# Temctrl_CPU.net
KiCad netlist of a schematic drawn in Altium Designer
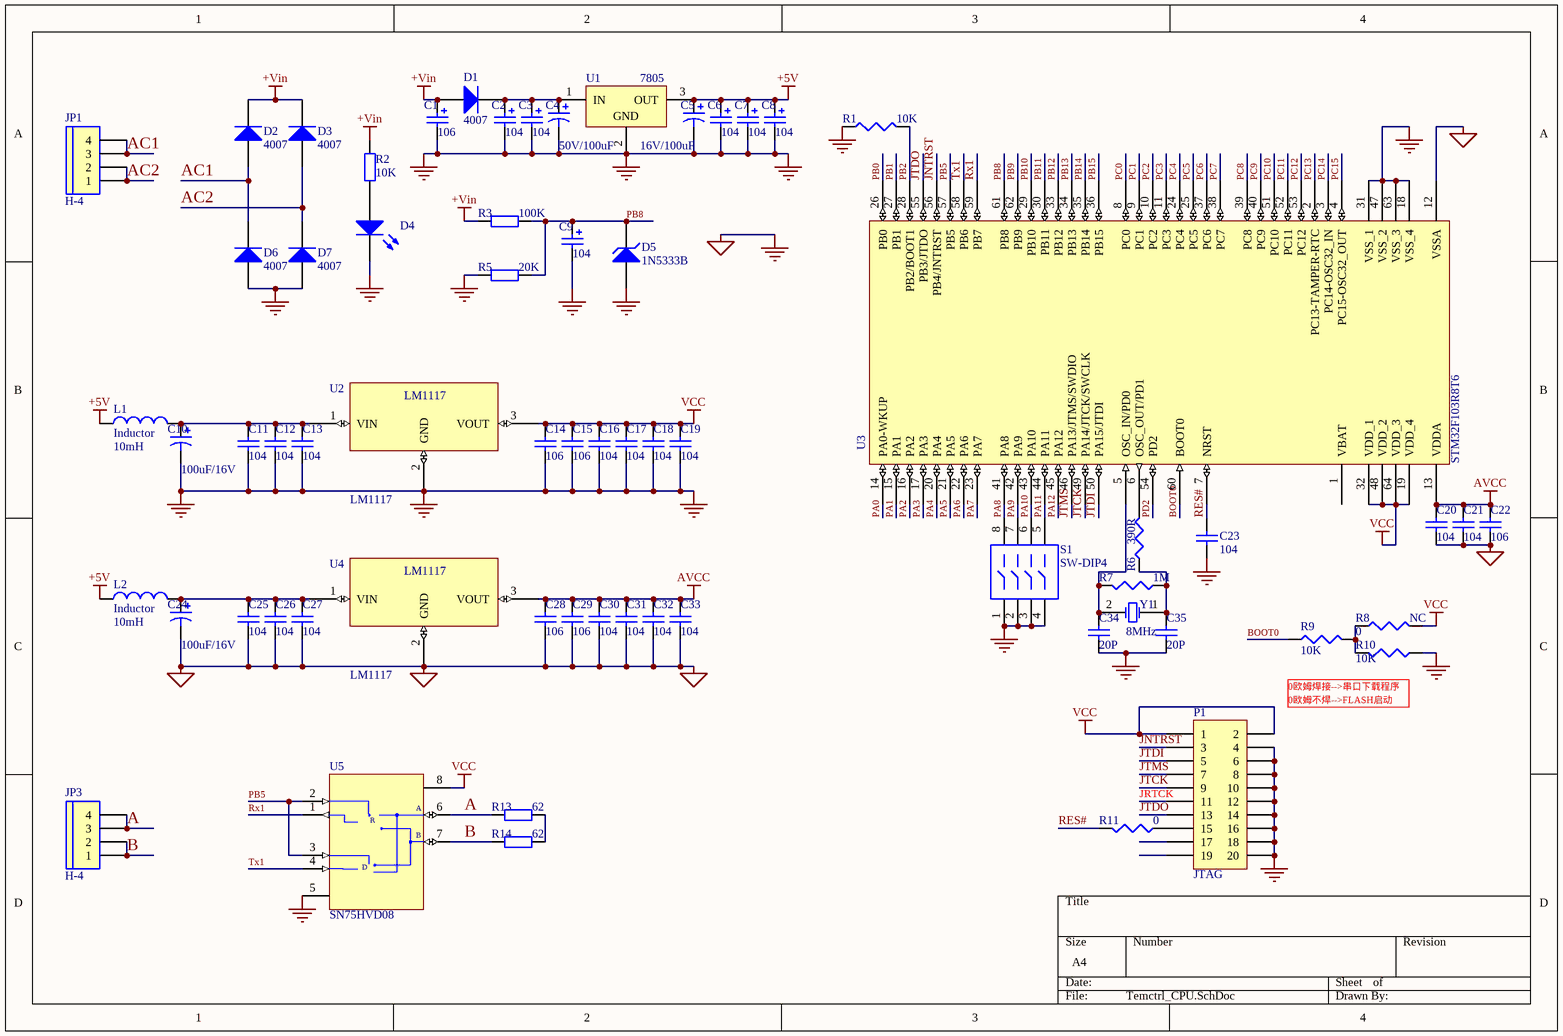
[diagram p0: Temctrl_CPU.SchDoc]

(export (version "E")
  (design (tool "Eeschema 10.0.6"))
  (components
    (comp (ref "C1")
      (value "106")
      (footprint "0805")
      (description "Polarized Capacitor (Axial)")
      (fields
        (field (name "MANUFACTURER") "Generic Components")
        (field (name "PUBLISHER") "Altium Hobart Technology Centre")
      )
      (libsource (lib "HGH") (part "Cap Pol2"))
    )
    (comp (ref "C2")
      (value "104")
      (footprint "0805")
      (description "Polarized Capacitor (Axial)")
      (fields
        (field (name "MANUFACTURER") "Generic Components")
        (field (name "PUBLISHER") "Altium Hobart Technology Centre")
      )
      (libsource (lib "HGH") (part "Cap Pol2"))
    )
    (comp (ref "C3")
      (value "104")
      (footprint "0805")
      (description "Polarized Capacitor (Axial)")
      (fields
        (field (name "MANUFACTURER") "Generic Components")
        (field (name "PUBLISHER") "Altium Hobart Technology Centre")
      )
      (libsource (lib "HGH") (part "Cap Pol2"))
    )
    (comp (ref "C4")
      (value "50V/100uF")
      (footprint "Temctrl:50V/100uF SOC")
      (description "Polarized Capacitor (Radial)")
      (fields (field (name "PUBLISHER") "Altium Limited"))
      (libsource (lib "Miscellaneous Devices") (part "Cap Pol1"))
    )
    (comp (ref "C5")
      (value "16V/100uF")
      (footprint "PCB封装库:100/16V   SOC")
      (description "Polarized Capacitor (Radial)")
      (fields (field (name "PUBLISHER") "Altium Limited"))
      (libsource (lib "Miscellaneous Devices") (part "Cap Pol1"))
    )
    (comp (ref "C6")
      (value "104")
      (footprint "0805")
      (description "Polarized Capacitor (Axial)")
      (fields
        (field (name "MANUFACTURER") "Generic Components")
        (field (name "PUBLISHER") "Altium Hobart Technology Centre")
      )
      (libsource (lib "HGH") (part "Cap Pol2"))
    )
    (comp (ref "C7")
      (value "104")
      (footprint "0805")
      (description "Polarized Capacitor (Axial)")
      (fields
        (field (name "MANUFACTURER") "Generic Components")
        (field (name "PUBLISHER") "Altium Hobart Technology Centre")
      )
      (libsource (lib "HGH") (part "Cap Pol2"))
    )
    (comp (ref "C8")
      (value "104")
      (footprint "0805")
      (description "Polarized Capacitor (Axial)")
      (fields
        (field (name "MANUFACTURER") "Generic Components")
        (field (name "PUBLISHER") "Altium Hobart Technology Centre")
      )
      (libsource (lib "HGH") (part "Cap Pol2"))
    )
    (comp (ref "C9")
      (value "104")
      (footprint "0805")
      (description "Polarized Capacitor (Axial)")
      (fields
        (field (name "MANUFACTURER") "Generic Components")
        (field (name "PUBLISHER") "Altium Hobart Technology Centre")
      )
      (libsource (lib "HGH") (part "Cap Pol2"))
    )
    (comp (ref "C10")
      (value "100uF/16V")
      (footprint "PCB封装库:100/16V   SOC")
      (description "Polarized Capacitor (Radial)")
      (fields (field (name "PUBLISHER") "Altium Limited"))
      (libsource (lib "Miscellaneous Devices") (part "Cap Pol1"))
    )
    (comp (ref "C11")
      (value "104")
      (footprint "0805")
      (description "Capacitor")
      (fields (field (name "PUBLISHER") "Altium Limited"))
      (libsource (lib "Miscellaneous Devices") (part "Cap"))
    )
    (comp (ref "C12")
      (value "104")
      (footprint "0805")
      (description "Capacitor")
      (fields (field (name "PUBLISHER") "Altium Limited"))
      (libsource (lib "Miscellaneous Devices") (part "Cap"))
    )
    (comp (ref "C13")
      (value "104")
      (footprint "0805")
      (description "Capacitor")
      (fields (field (name "PUBLISHER") "Altium Limited"))
      (libsource (lib "Miscellaneous Devices") (part "Cap"))
    )
    (comp (ref "C14")
      (value "106")
      (footprint "0805")
      (description "Capacitor")
      (fields (field (name "PUBLISHER") "Altium Limited"))
      (libsource (lib "Miscellaneous Devices") (part "Cap"))
    )
    (comp (ref "C15")
      (value "106")
      (footprint "0805")
      (description "Capacitor")
      (fields (field (name "PUBLISHER") "Altium Limited"))
      (libsource (lib "Miscellaneous Devices") (part "Cap"))
    )
    (comp (ref "C16")
      (value "104")
      (footprint "0805")
      (description "Capacitor")
      (fields (field (name "PUBLISHER") "Altium Limited"))
      (libsource (lib "Miscellaneous Devices") (part "Cap"))
    )
    (comp (ref "C17")
      (value "104")
      (footprint "0805")
      (description "Capacitor")
      (fields (field (name "PUBLISHER") "Altium Limited"))
      (libsource (lib "Miscellaneous Devices") (part "Cap"))
    )
    (comp (ref "C18")
      (value "104")
      (footprint "0805")
      (description "Capacitor")
      (fields (field (name "PUBLISHER") "Altium Limited"))
      (libsource (lib "Miscellaneous Devices") (part "Cap"))
    )
    (comp (ref "C19")
      (value "104")
      (footprint "0805")
      (description "Capacitor")
      (fields (field (name "PUBLISHER") "Altium Limited"))
      (libsource (lib "Miscellaneous Devices") (part "Cap"))
    )
    (comp (ref "C20")
      (value "104")
      (footprint "0805")
      (description "Capacitor (Semiconductor SIM Model)")
      (fields (field (name "PUBLISHER") "Altium Limited"))
      (libsource (lib "Miscellaneous Devices 04") (part "Cap Semi"))
    )
    (comp (ref "C21")
      (value "104")
      (footprint "0805")
      (description "Capacitor (Semiconductor SIM Model)")
      (fields (field (name "PUBLISHER") "Altium Limited"))
      (libsource (lib "Miscellaneous Devices 04") (part "Cap Semi"))
    )
    (comp (ref "C22")
      (value "106")
      (footprint "0805")
      (description "Capacitor (Semiconductor SIM Model)")
      (fields (field (name "PUBLISHER") "Altium Limited"))
      (libsource (lib "Miscellaneous Devices 04") (part "Cap Semi"))
    )
    (comp (ref "C23")
      (value "104")
      (footprint "0805")
      (description "Capacitor (Semiconductor SIM Model)")
      (fields (field (name "PUBLISHER") "Altium Limited"))
      (libsource (lib "Miscellaneous Devices 04") (part "Cap Semi"))
    )
    (comp (ref "C24")
      (value "100uF/16V")
      (footprint "PCB封装库:100/16V   SOC")
      (description "Polarized Capacitor (Radial)")
      (fields (field (name "PUBLISHER") "Altium Limited"))
      (libsource (lib "Miscellaneous Devices") (part "Cap Pol1"))
    )
    (comp (ref "C25")
      (value "104")
      (footprint "0805")
      (description "Capacitor")
      (fields (field (name "PUBLISHER") "Altium Limited"))
      (libsource (lib "Miscellaneous Devices") (part "Cap"))
    )
    (comp (ref "C26")
      (value "104")
      (footprint "0805")
      (description "Capacitor")
      (fields (field (name "PUBLISHER") "Altium Limited"))
      (libsource (lib "Miscellaneous Devices") (part "Cap"))
    )
    (comp (ref "C27")
      (value "104")
      (footprint "0805")
      (description "Capacitor")
      (fields (field (name "PUBLISHER") "Altium Limited"))
      (libsource (lib "Miscellaneous Devices") (part "Cap"))
    )
    (comp (ref "C28")
      (value "106")
      (footprint "0805")
      (description "Capacitor")
      (fields (field (name "PUBLISHER") "Altium Limited"))
      (libsource (lib "Miscellaneous Devices") (part "Cap"))
    )
    (comp (ref "C29")
      (value "106")
      (footprint "0805")
      (description "Capacitor")
      (fields (field (name "PUBLISHER") "Altium Limited"))
      (libsource (lib "Miscellaneous Devices") (part "Cap"))
    )
    (comp (ref "C30")
      (value "104")
      (footprint "0805")
      (description "Capacitor")
      (fields (field (name "PUBLISHER") "Altium Limited"))
      (libsource (lib "Miscellaneous Devices") (part "Cap"))
    )
    (comp (ref "C31")
      (value "104")
      (footprint "0805")
      (description "Capacitor")
      (fields (field (name "PUBLISHER") "Altium Limited"))
      (libsource (lib "Miscellaneous Devices") (part "Cap"))
    )
    (comp (ref "C32")
      (value "104")
      (footprint "0805")
      (description "Capacitor")
      (fields (field (name "PUBLISHER") "Altium Limited"))
      (libsource (lib "Miscellaneous Devices") (part "Cap"))
    )
    (comp (ref "C33")
      (value "104")
      (footprint "0805")
      (description "Capacitor")
      (fields (field (name "PUBLISHER") "Altium Limited"))
      (libsource (lib "Miscellaneous Devices") (part "Cap"))
    )
    (comp (ref "C34")
      (value "20P")
      (footprint "0805")
      (description "Capacitor (Semiconductor SIM Model)")
      (fields (field (name "PUBLISHER") "Altium Limited"))
      (libsource (lib "Miscellaneous Devices 04") (part "Cap Semi"))
    )
    (comp (ref "C35")
      (value "20P")
      (footprint "0805")
      (description "Capacitor (Semiconductor SIM Model)")
      (fields (field (name "PUBLISHER") "Altium Limited"))
      (libsource (lib "Miscellaneous Devices 04") (part "Cap Semi"))
    )
    (comp (ref "D1")
      (value "4007")
      (footprint "DIODE0.4")
      (description "Default Diode")
      (fields
        (field (name "MANUFACTURER") "Generic Components")
        (field (name "PUBLISHER") "Altium Hobart Technology Centre")
      )
      (libsource (lib "HGH") (part "Diode"))
    )
    (comp (ref "D2")
      (value "4007")
      (footprint "DIODE0.4")
      (description "Default Diode")
      (fields
        (field (name "MANUFACTURER") "Generic Components")
        (field (name "PUBLISHER") "Altium Hobart Technology Centre")
      )
      (libsource (lib "HGH") (part "Diode"))
    )
    (comp (ref "D3")
      (value "4007")
      (footprint "DIODE0.4")
      (description "Default Diode")
      (fields
        (field (name "MANUFACTURER") "Generic Components")
        (field (name "PUBLISHER") "Altium Hobart Technology Centre")
      )
      (libsource (lib "HGH") (part "Diode"))
    )
    (comp (ref "D4")
      (value "LED0")
      (footprint "LED0.1-0.22")
      (description "Typical INFRARED GaAs LED")
      (fields (field (name "PUBLISHER") "Altium Limited"))
      (libsource (lib "Miscellaneous Devices") (part "LED0"))
    )
    (comp (ref "D5")
      (value "1N5333B")
      (footprint "DIODE0.4")
      (description "Zener Diode")
      (fields (field (name "PUBLISHER") "Altium Limited"))
      (libsource (lib "Miscellaneous Devices") (part "D Zener"))
    )
    (comp (ref "D6")
      (value "4007")
      (footprint "DIODE0.4")
      (description "Default Diode")
      (fields
        (field (name "MANUFACTURER") "Generic Components")
        (field (name "PUBLISHER") "Altium Hobart Technology Centre")
      )
      (libsource (lib "HGH") (part "Diode"))
    )
    (comp (ref "D7")
      (value "4007")
      (footprint "DIODE0.4")
      (description "Default Diode")
      (fields
        (field (name "MANUFACTURER") "Generic Components")
        (field (name "PUBLISHER") "Altium Hobart Technology Centre")
      )
      (libsource (lib "HGH") (part "Diode"))
    )
    (comp (ref "JP1")
      (value "H-4")
      (footprint "P4")
      (description "Header, 4-Pin")
      (fields (field (name "MANUFACTURER") "Generic Components"))
      (libsource (lib "HGH") (part "H-4"))
    )
    (comp (ref "JP3")
      (value "H-4")
      (footprint "P4")
      (description "Header, 4-Pin")
      (fields (field (name "MANUFACTURER") "Generic Components"))
      (libsource (lib "HGH") (part "H-4"))
    )
    (comp (ref "L1")
      (value "Inductor")
      (footprint "0805")
      (fields (field (name "ALTIUM_VALUE") "10mH") (field (name "PUBLISHER") "Altium Limited"))
      (libsource (lib "Miscellaneous Devices") (part "Inductor"))
    )
    (comp (ref "L2")
      (value "Inductor")
      (footprint "0805")
      (fields (field (name "ALTIUM_VALUE") "10mH") (field (name "PUBLISHER") "Altium Limited"))
      (libsource (lib "Miscellaneous Devices") (part "Inductor"))
    )
    (comp (ref "P1")
      (value "JTAG")
      (footprint "HDR2X10")
      (description "Header, 10-Pin, Dual row")
      (fields (field (name "PUBLISHER") "Altium Limited"))
      (libsource (lib "Miscellaneous Connectors") (part "Header 10X2"))
    )
    (comp (ref "R1")
      (value "10K")
      (footprint "0805")
      (description "Resistor")
      (fields (field (name "PUBLISHER") "Altium Limited"))
      (libsource (lib "Miscellaneous Devices 04") (part "Res3"))
    )
    (comp (ref "R2")
      (value "10K")
      (footprint "0805")
      (description "Resistor")
      (fields
        (field (name "MANUFACTURER") "Generic Components")
        (field (name "PUBLISHER") "Altium Hobart Technology Centre")
      )
      (libsource (lib "") (part "Res_1"))
    )
    (comp (ref "R3")
      (value "100K")
      (footprint "0805")
      (description "Resistor")
      (fields
        (field (name "MANUFACTURER") "Generic Components")
        (field (name "PUBLISHER") "Altium Hobart Technology Centre")
      )
      (libsource (lib "HGH") (part "Res"))
    )
    (comp (ref "R5")
      (value "20K")
      (footprint "0805")
      (description "Resistor")
      (fields
        (field (name "MANUFACTURER") "Generic Components")
        (field (name "PUBLISHER") "Altium Hobart Technology Centre")
      )
      (libsource (lib "HGH") (part "Res"))
    )
    (comp (ref "R6")
      (value "390R")
      (footprint "0805")
      (description "Resistor")
      (fields (field (name "PUBLISHER") "Altium Limited"))
      (libsource (lib "Miscellaneous Devices 04") (part "Res3"))
    )
    (comp (ref "R7")
      (value "1M")
      (footprint "0805")
      (description "Resistor")
      (fields (field (name "PUBLISHER") "Altium Limited"))
      (libsource (lib "Miscellaneous Devices 04") (part "Res3"))
    )
    (comp (ref "R8")
      (value "NC")
      (footprint "0805")
      (description "Resistor")
      (fields (field (name "ALTIUM_VALUE") "0") (field (name "PUBLISHER") "Altium Limited"))
      (libsource (lib "Miscellaneous Devices 04") (part "Res3"))
    )
    (comp (ref "R9")
      (value "10K")
      (footprint "0805")
      (description "Resistor")
      (fields (field (name "PUBLISHER") "Altium Limited"))
      (libsource (lib "Miscellaneous Devices 04") (part "Res3"))
    )
    (comp (ref "R10")
      (value "10K")
      (footprint "0805")
      (description "Resistor")
      (fields (field (name "PUBLISHER") "Altium Limited"))
      (libsource (lib "Miscellaneous Devices 04") (part "Res3"))
    )
    (comp (ref "R11")
      (value "0")
      (footprint "0805")
      (description "Resistor")
      (fields (field (name "PUBLISHER") "Altium Limited"))
      (libsource (lib "Miscellaneous Devices 04") (part "Res3"))
    )
    (comp (ref "R13")
      (value "62")
      (footprint "0805")
      (description "Resistor")
      (fields
        (field (name "MANUFACTURER") "Generic Components")
        (field (name "PUBLISHER") "Altium Hobart Technology Centre")
      )
      (libsource (lib "HGH") (part "Res"))
    )
    (comp (ref "R14")
      (value "62")
      (footprint "0805")
      (description "Resistor")
      (fields
        (field (name "MANUFACTURER") "Generic Components")
        (field (name "PUBLISHER") "Altium Hobart Technology Centre")
      )
      (libsource (lib "HGH") (part "Res"))
    )
    (comp (ref "S1")
      (value "SW-DIP4")
      (footprint "SW-DIP-4")
      (description "DIP Switch,4-bit")
      (fields (field (name "MANUFACTURER") "Generic Components"))
      (libsource (lib "HGH") (part "SW-DIP4"))
    )
    (comp (ref "U1") (value "7805") (footprint "SIP-W3 /SRQ25") (libsource (lib "HGH") (part "78*05")))
    (comp (ref "U2") (value "LM1117") (footprint "DSO-G3/P2.3") (libsource (lib "HGH") (part "LM1117")))
    (comp (ref "U3")
      (value "STM32F103R8T6")
      (footprint "LQFP64_N")
      (description "STM32 ARM-based 32-bit MCU with 64 Kbytes Flash, 64-pin LQFP, Industrial Temperature")
      (fields (field (name "PUBLISHER") "Altium Limited"))
      (libsource (lib "ST Microcontroller 32-Bit STM32") (part "STM32F103R8T6"))
    )
    (comp (ref "U4") (value "LM1117") (footprint "DSO-G3/P2.3") (libsource (lib "HGH") (part "LM1117")))
    (comp (ref "U5")
      (value "SN75HVD08")
      (footprint "SOP8-max485")
      (description "Low-Power, Slew-Rate-Limited RS-485/RS-422 Transceiver")
      (fields
        (field (name "MANUFACTURER") "Maxim")
        (field (name "PUBLISHER") "Altium Hobart Technology Centre")
      )
      (libsource (lib "HGH") (part "MAX485CPA"))
    )
    (comp (ref "Y1")
      (value "8MHz")
      (footprint "XTL")
      (description "Crystal Oscillator")
      (fields
        (field (name "MANUFACTURER") "Generic Components")
        (field (name "Comment") "XTAL")
        (field (name "PUBLISHER") "Altium Hobart Technology Centre")
      )
      (libsource (lib "HGH") (part "XTAL"))
    )
  )
  (nets
    (net (code "1") (name "+5V") (class "Default")
      (node (ref "C5") (pin "1") (pinfunction "1_1") (pintype "passive"))
      (node (ref "C6") (pin "1") (pinfunction "1_1") (pintype "passive"))
      (node (ref "C7") (pin "1") (pinfunction "1_1") (pintype "passive"))
      (node (ref "C8") (pin "1") (pinfunction "1_1") (pintype "passive"))
      (node (ref "L1") (pin "1") (pinfunction "1_1") (pintype "passive"))
      (node (ref "L2") (pin "1") (pinfunction "1_1") (pintype "passive"))
      (node (ref "U1") (pin "3") (pinfunction "OUT_3") (pintype "power_in"))
    )
    (net (code "2") (name "+Vin") (class "Default")
      (node (ref "C1") (pin "1") (pinfunction "1_1") (pintype "passive"))
      (node (ref "D1") (pin "1") (pinfunction "A_1") (pintype "passive"))
      (node (ref "D2") (pin "2") (pinfunction "K_2") (pintype "passive"))
      (node (ref "D3") (pin "2") (pinfunction "K_2") (pintype "passive"))
      (node (ref "R2") (pin "1") (pinfunction "1_1") (pintype "passive"))
      (node (ref "R3") (pin "2") (pinfunction "2_2") (pintype "passive"))
    )
    (net (code "3") (name "/A") (class "Default")
      (node (ref "JP3") (pin "3") (pinfunction "3_3") (pintype "passive"))
      (node (ref "JP3") (pin "4") (pinfunction "4_4") (pintype "passive"))
      (node (ref "R13") (pin "2") (pinfunction "2_2") (pintype "passive"))
      (node (ref "U5") (pin "6") (pinfunction "A_6") (pintype "bidirectional"))
    )
    (net (code "4") (name "/AC1") (class "Default")
      (node (ref "D2") (pin "1") (pinfunction "A_1") (pintype "passive"))
      (node (ref "D6") (pin "2") (pinfunction "K_2") (pintype "passive"))
      (node (ref "JP1") (pin "3") (pinfunction "3_3") (pintype "passive"))
      (node (ref "JP1") (pin "4") (pinfunction "4_4") (pintype "passive"))
    )
    (net (code "5") (name "/AC2") (class "Default")
      (node (ref "D3") (pin "1") (pinfunction "A_1") (pintype "passive"))
      (node (ref "D7") (pin "2") (pinfunction "K_2") (pintype "passive"))
      (node (ref "JP1") (pin "1") (pinfunction "1_1") (pintype "passive"))
      (node (ref "JP1") (pin "2") (pinfunction "2_2") (pintype "passive"))
    )
    (net (code "6") (name "/B") (class "Default")
      (node (ref "JP3") (pin "1") (pinfunction "1_1") (pintype "passive"))
      (node (ref "JP3") (pin "2") (pinfunction "2_2") (pintype "passive"))
      (node (ref "R14") (pin "2") (pinfunction "2_2") (pintype "passive"))
      (node (ref "U5") (pin "7") (pinfunction "B_7") (pintype "bidirectional"))
    )
    (net (code "7") (name "/BOOT0") (class "Default")
      (node (ref "R9") (pin "1") (pinfunction "1_1") (pintype "passive"))
      (node (ref "U3") (pin "60") (pinfunction "BOOT0_60") (pintype "input"))
    )
    (net (code "8") (name "/JNTRST") (class "Default")
      (node (ref "P1") (pin "3") (pinfunction "3_3") (pintype "passive"))
      (node (ref "U3") (pin "56") (pinfunction "PB4/JNTRST_56") (pintype "bidirectional"))
    )
    (net (code "9") (name "/JTCK") (class "Default")
      (node (ref "P1") (pin "9") (pinfunction "9_9") (pintype "passive"))
      (node (ref "U3") (pin "49") (pinfunction "PA14/JTCK/SWCLK_49") (pintype "bidirectional"))
    )
    (net (code "10") (name "/JTDI") (class "Default")
      (node (ref "P1") (pin "5") (pinfunction "5_5") (pintype "passive"))
      (node (ref "U3") (pin "50") (pinfunction "PA15/JTDI_50") (pintype "bidirectional"))
    )
    (net (code "11") (name "/JTDO") (class "Default")
      (node (ref "P1") (pin "13") (pinfunction "13_13") (pintype "passive"))
      (node (ref "U3") (pin "55") (pinfunction "PB3/JTDO_55") (pintype "bidirectional"))
    )
    (net (code "12") (name "/JTMS") (class "Default")
      (node (ref "P1") (pin "7") (pinfunction "7_7") (pintype "passive"))
      (node (ref "U3") (pin "46") (pinfunction "PA13/JTMS/SWDIO_46") (pintype "bidirectional"))
    )
    (net (code "13") (name "/PA0") (class "Default")
      (node (ref "U3") (pin "14") (pinfunction "PA0-WKUP_14") (pintype "bidirectional"))
    )
    (net (code "14") (name "/PA1") (class "Default")
      (node (ref "U3") (pin "15") (pinfunction "PA1_15") (pintype "bidirectional"))
    )
    (net (code "15") (name "/PA2") (class "Default")
      (node (ref "U3") (pin "16") (pinfunction "PA2_16") (pintype "bidirectional"))
    )
    (net (code "16") (name "/PA3") (class "Default")
      (node (ref "U3") (pin "17") (pinfunction "PA3_17") (pintype "bidirectional"))
    )
    (net (code "17") (name "/PA4") (class "Default")
      (node (ref "U3") (pin "20") (pinfunction "PA4_20") (pintype "bidirectional"))
    )
    (net (code "18") (name "/PA5") (class "Default")
      (node (ref "U3") (pin "21") (pinfunction "PA5_21") (pintype "bidirectional"))
    )
    (net (code "19") (name "/PA6") (class "Default")
      (node (ref "U3") (pin "22") (pinfunction "PA6_22") (pintype "bidirectional"))
    )
    (net (code "20") (name "/PA7") (class "Default")
      (node (ref "U3") (pin "23") (pinfunction "PA7_23") (pintype "bidirectional"))
    )
    (net (code "21") (name "/PA8") (class "Default")
      (node (ref "S1") (pin "8") (pinfunction "8_8") (pintype "passive"))
      (node (ref "U3") (pin "41") (pinfunction "PA8_41") (pintype "bidirectional"))
    )
    (net (code "22") (name "/PA9") (class "Default")
      (node (ref "S1") (pin "7") (pinfunction "7_7") (pintype "passive"))
      (node (ref "U3") (pin "42") (pinfunction "PA9_42") (pintype "bidirectional"))
    )
    (net (code "23") (name "/PA10") (class "Default")
      (node (ref "S1") (pin "6") (pinfunction "6_6") (pintype "passive"))
      (node (ref "U3") (pin "43") (pinfunction "PA10_43") (pintype "bidirectional"))
    )
    (net (code "24") (name "/PA11") (class "Default")
      (node (ref "S1") (pin "5") (pinfunction "5_5") (pintype "passive"))
      (node (ref "U3") (pin "44") (pinfunction "PA11_44") (pintype "bidirectional"))
    )
    (net (code "25") (name "/PA12") (class "Default")
      (node (ref "U3") (pin "45") (pinfunction "PA12_45") (pintype "bidirectional"))
    )
    (net (code "26") (name "/PB0") (class "Default")
      (node (ref "U3") (pin "26") (pinfunction "PB0_26") (pintype "bidirectional"))
    )
    (net (code "27") (name "/PB1") (class "Default")
      (node (ref "U3") (pin "27") (pinfunction "PB1_27") (pintype "bidirectional"))
    )
    (net (code "28") (name "/PB2") (class "Default")
      (node (ref "R1") (pin "2") (pinfunction "2_2") (pintype "passive"))
      (node (ref "U3") (pin "28") (pinfunction "PB2/BOOT1_28") (pintype "bidirectional"))
    )
    (net (code "29") (name "/PB5") (class "Default")
      (node (ref "U3") (pin "57") (pinfunction "PB5_57") (pintype "bidirectional"))
      (node (ref "U5") (pin "2") (pinfunction "~{RE}_2") (pintype "input"))
      (node (ref "U5") (pin "3") (pinfunction "DE_3") (pintype "input"))
    )
    (net (code "30") (name "/PB8") (class "Default")
      (node (ref "C9") (pin "1") (pinfunction "1_1") (pintype "passive"))
      (node (ref "D5") (pin "2") (pinfunction "K_2") (pintype "passive"))
      (node (ref "R3") (pin "1") (pinfunction "1_1") (pintype "passive"))
      (node (ref "R5") (pin "1") (pinfunction "1_1") (pintype "passive"))
      (node (ref "U3") (pin "61") (pinfunction "PB8_61") (pintype "bidirectional"))
    )
    (net (code "31") (name "/PB9") (class "Default")
      (node (ref "U3") (pin "62") (pinfunction "PB9_62") (pintype "bidirectional"))
    )
    (net (code "32") (name "/PB10") (class "Default")
      (node (ref "U3") (pin "29") (pinfunction "PB10_29") (pintype "bidirectional"))
    )
    (net (code "33") (name "/PB11") (class "Default")
      (node (ref "U3") (pin "30") (pinfunction "PB11_30") (pintype "bidirectional"))
    )
    (net (code "34") (name "/PB12") (class "Default")
      (node (ref "U3") (pin "33") (pinfunction "PB12_33") (pintype "bidirectional"))
    )
    (net (code "35") (name "/PB13") (class "Default")
      (node (ref "U3") (pin "34") (pinfunction "PB13_34") (pintype "bidirectional"))
    )
    (net (code "36") (name "/PB14") (class "Default")
      (node (ref "U3") (pin "35") (pinfunction "PB14_35") (pintype "bidirectional"))
    )
    (net (code "37") (name "/PB15") (class "Default")
      (node (ref "U3") (pin "36") (pinfunction "PB15_36") (pintype "bidirectional"))
    )
    (net (code "38") (name "/PC0") (class "Default")
      (node (ref "U3") (pin "8") (pinfunction "PC0_8") (pintype "bidirectional"))
    )
    (net (code "39") (name "/PC1") (class "Default")
      (node (ref "U3") (pin "9") (pinfunction "PC1_9") (pintype "bidirectional"))
    )
    (net (code "40") (name "/PC2") (class "Default")
      (node (ref "U3") (pin "10") (pinfunction "PC2_10") (pintype "bidirectional"))
    )
    (net (code "41") (name "/PC3") (class "Default")
      (node (ref "U3") (pin "11") (pinfunction "PC3_11") (pintype "bidirectional"))
    )
    (net (code "42") (name "/PC4") (class "Default")
      (node (ref "U3") (pin "24") (pinfunction "PC4_24") (pintype "bidirectional"))
    )
    (net (code "43") (name "/PC5") (class "Default")
      (node (ref "U3") (pin "25") (pinfunction "PC5_25") (pintype "bidirectional"))
    )
    (net (code "44") (name "/PC6") (class "Default")
      (node (ref "U3") (pin "37") (pinfunction "PC6_37") (pintype "bidirectional"))
    )
    (net (code "45") (name "/PC7") (class "Default")
      (node (ref "U3") (pin "38") (pinfunction "PC7_38") (pintype "bidirectional"))
    )
    (net (code "46") (name "/PC8") (class "Default")
      (node (ref "U3") (pin "39") (pinfunction "PC8_39") (pintype "bidirectional"))
    )
    (net (code "47") (name "/PC9") (class "Default")
      (node (ref "U3") (pin "40") (pinfunction "PC9_40") (pintype "bidirectional"))
    )
    (net (code "48") (name "/PC10") (class "Default")
      (node (ref "U3") (pin "51") (pinfunction "PC10_51") (pintype "bidirectional"))
    )
    (net (code "49") (name "/PC11") (class "Default")
      (node (ref "U3") (pin "52") (pinfunction "PC11_52") (pintype "bidirectional"))
    )
    (net (code "50") (name "/PC12") (class "Default")
      (node (ref "U3") (pin "53") (pinfunction "PC12_53") (pintype "bidirectional"))
    )
    (net (code "51") (name "/PC13") (class "Default")
      (node (ref "U3") (pin "2") (pinfunction "PC13-TAMPER-RTC_2") (pintype "bidirectional"))
    )
    (net (code "52") (name "/PC14") (class "Default")
      (node (ref "U3") (pin "3") (pinfunction "PC14-OSC32_IN_3") (pintype "bidirectional"))
    )
    (net (code "53") (name "/PC15") (class "Default")
      (node (ref "U3") (pin "4") (pinfunction "PC15-OSC32_OUT_4") (pintype "bidirectional"))
    )
    (net (code "54") (name "/PD2") (class "Default")
      (node (ref "U3") (pin "54") (pinfunction "PD2_54") (pintype "bidirectional"))
    )
    (net (code "55") (name "/RES#") (class "Default")
      (node (ref "C23") (pin "1") (pinfunction "1_1") (pintype "passive"))
      (node (ref "R11") (pin "2") (pinfunction "2_2") (pintype "passive"))
      (node (ref "U3") (pin "7") (pinfunction "NRST_7") (pintype "bidirectional"))
    )
    (net (code "56") (name "/Rx1") (class "Default")
      (node (ref "U3") (pin "59") (pinfunction "PB7_59") (pintype "bidirectional"))
      (node (ref "U5") (pin "1") (pinfunction "RO_1") (pintype "output"))
    )
    (net (code "57") (name "/Tx1") (class "Default")
      (node (ref "U3") (pin "58") (pinfunction "PB6_58") (pintype "bidirectional"))
      (node (ref "U5") (pin "4") (pinfunction "DI_4") (pintype "input"))
    )
    (net (code "58") (name "AGND") (class "Default")
      (node (ref "C1") (pin "2") (pinfunction "2_2") (pintype "passive"))
      (node (ref "C10") (pin "2") (pinfunction "2_2") (pintype "passive"))
      (node (ref "C11") (pin "2") (pinfunction "2_2") (pintype "passive"))
      (node (ref "C12") (pin "2") (pinfunction "2_2") (pintype "passive"))
      (node (ref "C13") (pin "2") (pinfunction "2_2") (pintype "passive"))
      (node (ref "C14") (pin "2") (pinfunction "2_2") (pintype "passive"))
      (node (ref "C15") (pin "2") (pinfunction "2_2") (pintype "passive"))
      (node (ref "C16") (pin "2") (pinfunction "2_2") (pintype "passive"))
      (node (ref "C17") (pin "2") (pinfunction "2_2") (pintype "passive"))
      (node (ref "C18") (pin "2") (pinfunction "2_2") (pintype "passive"))
      (node (ref "C19") (pin "2") (pinfunction "2_2") (pintype "passive"))
      (node (ref "C2") (pin "2") (pinfunction "2_2") (pintype "passive"))
      (node (ref "C20") (pin "1") (pinfunction "1_1") (pintype "passive"))
      (node (ref "C21") (pin "1") (pinfunction "1_1") (pintype "passive"))
      (node (ref "C22") (pin "1") (pinfunction "1_1") (pintype "passive"))
      (node (ref "C23") (pin "2") (pinfunction "2_2") (pintype "passive"))
      (node (ref "C24") (pin "2") (pinfunction "2_2") (pintype "passive"))
      (node (ref "C25") (pin "2") (pinfunction "2_2") (pintype "passive"))
      (node (ref "C26") (pin "2") (pinfunction "2_2") (pintype "passive"))
      (node (ref "C27") (pin "2") (pinfunction "2_2") (pintype "passive"))
      (node (ref "C28") (pin "2") (pinfunction "2_2") (pintype "passive"))
      (node (ref "C29") (pin "2") (pinfunction "2_2") (pintype "passive"))
      (node (ref "C3") (pin "2") (pinfunction "2_2") (pintype "passive"))
      (node (ref "C30") (pin "2") (pinfunction "2_2") (pintype "passive"))
      (node (ref "C31") (pin "2") (pinfunction "2_2") (pintype "passive"))
      (node (ref "C32") (pin "2") (pinfunction "2_2") (pintype "passive"))
      (node (ref "C33") (pin "2") (pinfunction "2_2") (pintype "passive"))
      (node (ref "C34") (pin "1") (pinfunction "1_1") (pintype "passive"))
      (node (ref "C35") (pin "1") (pinfunction "1_1") (pintype "passive"))
      (node (ref "C4") (pin "2") (pinfunction "2_2") (pintype "passive"))
      (node (ref "C5") (pin "2") (pinfunction "2_2") (pintype "passive"))
      (node (ref "C6") (pin "2") (pinfunction "2_2") (pintype "passive"))
      (node (ref "C7") (pin "2") (pinfunction "2_2") (pintype "passive"))
      (node (ref "C8") (pin "2") (pinfunction "2_2") (pintype "passive"))
      (node (ref "C9") (pin "2") (pinfunction "2_2") (pintype "passive"))
      (node (ref "D4") (pin "2") (pinfunction "K_2") (pintype "passive"))
      (node (ref "D5") (pin "1") (pinfunction "A_1") (pintype "passive"))
      (node (ref "D6") (pin "1") (pinfunction "A_1") (pintype "passive"))
      (node (ref "D7") (pin "1") (pinfunction "A_1") (pintype "passive"))
      (node (ref "P1") (pin "10") (pinfunction "10_10") (pintype "passive"))
      (node (ref "P1") (pin "12") (pinfunction "12_12") (pintype "passive"))
      (node (ref "P1") (pin "14") (pinfunction "14_14") (pintype "passive"))
      (node (ref "P1") (pin "16") (pinfunction "16_16") (pintype "passive"))
      (node (ref "P1") (pin "18") (pinfunction "18_18") (pintype "passive"))
      (node (ref "P1") (pin "20") (pinfunction "20_20") (pintype "passive"))
      (node (ref "P1") (pin "4") (pinfunction "4_4") (pintype "passive"))
      (node (ref "P1") (pin "6") (pinfunction "6_6") (pintype "passive"))
      (node (ref "P1") (pin "8") (pinfunction "8_8") (pintype "passive"))
      (node (ref "R1") (pin "1") (pinfunction "1_1") (pintype "passive"))
      (node (ref "R10") (pin "1") (pinfunction "1_1") (pintype "passive"))
      (node (ref "R5") (pin "2") (pinfunction "2_2") (pintype "passive"))
      (node (ref "S1") (pin "1") (pinfunction "1_1") (pintype "passive"))
      (node (ref "S1") (pin "2") (pinfunction "2_2") (pintype "passive"))
      (node (ref "S1") (pin "3") (pinfunction "3_3") (pintype "passive"))
      (node (ref "S1") (pin "4") (pinfunction "4_4") (pintype "passive"))
      (node (ref "U1") (pin "2") (pinfunction "GND_2") (pintype "power_in"))
      (node (ref "U2") (pin "2") (pinfunction "GND_2") (pintype "bidirectional"))
      (node (ref "U3") (pin "12") (pinfunction "VSSA_12") (pintype "power_in"))
      (node (ref "U3") (pin "18") (pinfunction "VSS_4_18") (pintype "power_in"))
      (node (ref "U3") (pin "31") (pinfunction "VSS_1_31") (pintype "power_in"))
      (node (ref "U3") (pin "47") (pinfunction "VSS_2_47") (pintype "power_in"))
      (node (ref "U3") (pin "63") (pinfunction "VSS_3_63") (pintype "power_in"))
      (node (ref "U4") (pin "2") (pinfunction "GND_2") (pintype "bidirectional"))
      (node (ref "U5") (pin "5") (pinfunction "GND_5") (pintype "power_in"))
    )
    (net (code "59") (name "AVCC") (class "Default")
      (node (ref "C20") (pin "2") (pinfunction "2_2") (pintype "passive"))
      (node (ref "C21") (pin "2") (pinfunction "2_2") (pintype "passive"))
      (node (ref "C22") (pin "2") (pinfunction "2_2") (pintype "passive"))
      (node (ref "C28") (pin "1") (pinfunction "1_1") (pintype "passive"))
      (node (ref "C29") (pin "1") (pinfunction "1_1") (pintype "passive"))
      (node (ref "C30") (pin "1") (pinfunction "1_1") (pintype "passive"))
      (node (ref "C31") (pin "1") (pinfunction "1_1") (pintype "passive"))
      (node (ref "C32") (pin "1") (pinfunction "1_1") (pintype "passive"))
      (node (ref "C33") (pin "1") (pinfunction "1_1") (pintype "passive"))
      (node (ref "U3") (pin "13") (pinfunction "VDDA_13") (pintype "power_in"))
      (node (ref "U4") (pin "3") (pinfunction "VOUT_3") (pintype "bidirectional"))
    )
    (net (code "60") (name "Net-(D1-K)") (class "Default")
      (node (ref "C2") (pin "1") (pinfunction "1_1") (pintype "passive"))
      (node (ref "C3") (pin "1") (pinfunction "1_1") (pintype "passive"))
      (node (ref "C4") (pin "1") (pinfunction "1_1") (pintype "passive"))
      (node (ref "D1") (pin "2") (pinfunction "K_2") (pintype "passive"))
      (node (ref "U1") (pin "1") (pinfunction "IN_1") (pintype "power_in"))
    )
    (net (code "61") (name "Net-(D4-A)") (class "Default")
      (node (ref "D4") (pin "1") (pinfunction "A_1") (pintype "passive"))
      (node (ref "R2") (pin "2") (pinfunction "2_2") (pintype "passive"))
    )
    (net (code "62") (name "Net-(P1-Pad15)") (class "Default")
      (node (ref "P1") (pin "15") (pinfunction "15_15") (pintype "passive"))
      (node (ref "R11") (pin "1") (pinfunction "1_1") (pintype "passive"))
    )
    (net (code "63") (name "Net-(R10-Pad2)") (class "Default")
      (node (ref "R10") (pin "2") (pinfunction "2_2") (pintype "passive"))
      (node (ref "R8") (pin "1") (pinfunction "1_1") (pintype "passive"))
      (node (ref "R9") (pin "2") (pinfunction "2_2") (pintype "passive"))
    )
    (net (code "64") (name "Net-(R13-Pad1)") (class "Default")
      (node (ref "R13") (pin "1") (pinfunction "1_1") (pintype "passive"))
      (node (ref "R14") (pin "1") (pinfunction "1_1") (pintype "passive"))
    )
    (net (code "65") (name "Net-(U2-VIN)") (class "Default")
      (node (ref "C10") (pin "1") (pinfunction "1_1") (pintype "passive"))
      (node (ref "C11") (pin "1") (pinfunction "1_1") (pintype "passive"))
      (node (ref "C12") (pin "1") (pinfunction "1_1") (pintype "passive"))
      (node (ref "C13") (pin "1") (pinfunction "1_1") (pintype "passive"))
      (node (ref "L1") (pin "2") (pinfunction "2_2") (pintype "passive"))
      (node (ref "U2") (pin "1") (pinfunction "VIN_1") (pintype "bidirectional"))
    )
    (net (code "66") (name "Net-(U3-OSC_IN{slash}PD0)") (class "Default")
      (node (ref "C34") (pin "2") (pinfunction "2_2") (pintype "passive"))
      (node (ref "R7") (pin "2") (pinfunction "2_2") (pintype "passive"))
      (node (ref "U3") (pin "5") (pinfunction "OSC_IN/PD0_5") (pintype "input"))
      (node (ref "Y1") (pin "2") (pinfunction "OSC2_2") (pintype "passive"))
    )
    (net (code "67") (name "Net-(U3-OSC_OUT{slash}PD1)") (class "Default")
      (node (ref "R6") (pin "2") (pinfunction "2_2") (pintype "passive"))
      (node (ref "U3") (pin "6") (pinfunction "OSC_OUT/PD1_6") (pintype "output"))
    )
    (net (code "68") (name "Net-(U4-VIN)") (class "Default")
      (node (ref "C24") (pin "1") (pinfunction "1_1") (pintype "passive"))
      (node (ref "C25") (pin "1") (pinfunction "1_1") (pintype "passive"))
      (node (ref "C26") (pin "1") (pinfunction "1_1") (pintype "passive"))
      (node (ref "C27") (pin "1") (pinfunction "1_1") (pintype "passive"))
      (node (ref "L2") (pin "2") (pinfunction "2_2") (pintype "passive"))
      (node (ref "U4") (pin "1") (pinfunction "VIN_1") (pintype "bidirectional"))
    )
    (net (code "69") (name "Net-(Y1-OSC1)") (class "Default")
      (node (ref "C35") (pin "2") (pinfunction "2_2") (pintype "passive"))
      (node (ref "R6") (pin "1") (pinfunction "1_1") (pintype "passive"))
      (node (ref "R7") (pin "1") (pinfunction "1_1") (pintype "passive"))
      (node (ref "Y1") (pin "1") (pinfunction "OSC1_1") (pintype "passive"))
    )
    (net (code "70") (name "VCC") (class "Default")
      (node (ref "C14") (pin "1") (pinfunction "1_1") (pintype "passive"))
      (node (ref "C15") (pin "1") (pinfunction "1_1") (pintype "passive"))
      (node (ref "C16") (pin "1") (pinfunction "1_1") (pintype "passive"))
      (node (ref "C17") (pin "1") (pinfunction "1_1") (pintype "passive"))
      (node (ref "C18") (pin "1") (pinfunction "1_1") (pintype "passive"))
      (node (ref "C19") (pin "1") (pinfunction "1_1") (pintype "passive"))
      (node (ref "P1") (pin "1") (pinfunction "1_1") (pintype "passive"))
      (node (ref "P1") (pin "2") (pinfunction "2_2") (pintype "passive"))
      (node (ref "R8") (pin "2") (pinfunction "2_2") (pintype "passive"))
      (node (ref "U2") (pin "3") (pinfunction "VOUT_3") (pintype "bidirectional"))
      (node (ref "U3") (pin "19") (pinfunction "VDD_4_19") (pintype "power_in"))
      (node (ref "U3") (pin "32") (pinfunction "VDD_1_32") (pintype "power_in"))
      (node (ref "U3") (pin "48") (pinfunction "VDD_2_48") (pintype "power_in"))
      (node (ref "U3") (pin "64") (pinfunction "VDD_3_64") (pintype "power_in"))
      (node (ref "U5") (pin "8") (pinfunction "VCC_8") (pintype "power_in"))
    )
    (net (code "71") (name "unconnected-(P1-Pad11)") (class "Default")
      (node (ref "P1") (pin "11") (pinfunction "11_11") (pintype "passive"))
    )
    (net (code "72") (name "unconnected-(P1-Pad17)") (class "Default")
      (node (ref "P1") (pin "17") (pinfunction "17_17") (pintype "passive"))
    )
    (net (code "73") (name "unconnected-(P1-Pad19)") (class "Default")
      (node (ref "P1") (pin "19") (pinfunction "19_19") (pintype "passive"))
    )
    (net (code "74") (name "unconnected-(U3-VBAT-Pad1)") (class "Default")
      (node (ref "U3") (pin "1") (pinfunction "VBAT_1") (pintype "power_in"))
    )
  )
)
